# adapter-50-100mil-x6.net
KiCad netlist of a schematic drawn in Altium Designer
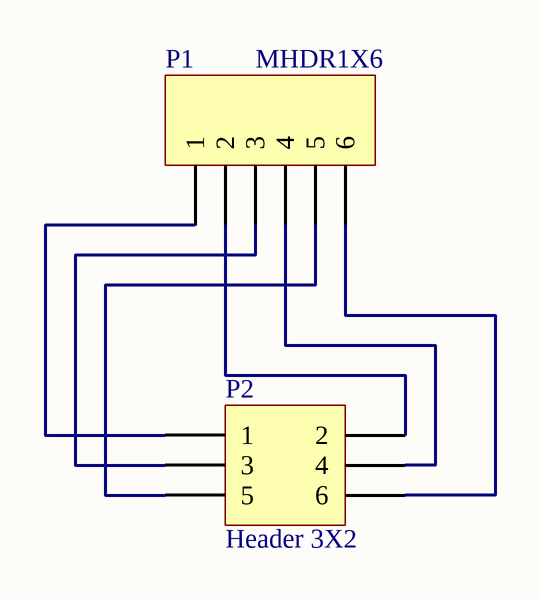
[diagram p0: adapter-50-100mil-x6.SchDoc]

(export (version "E")
  (design (tool "Eeschema 10.0.6"))
  (components
    (comp (ref "P1")
      (value "MHDR1X6")
      (footprint "MHDR1X6")
      (description "Header, 6-Pin")
      (fields (field (name "PUBLISHER") "Altium Limited"))
      (libsource (lib "Miscellaneous Connectors") (part "MHDR1X6"))
    )
    (comp (ref "P2")
      (value "Header 3X2")
      (footprint "HDR2X3")
      (description "Header, 3-Pin, Dual row")
      (fields (field (name "PUBLISHER") "Altium Limited"))
      (libsource (lib "Miscellaneous Connectors") (part "Header 3X2"))
    )
  )
  (nets
    (net (code "1") (name "Net-(P1-Pad1)") (class "Default")
      (node (ref "P1") (pin "1") (pinfunction "1_1") (pintype "passive"))
      (node (ref "P2") (pin "1") (pinfunction "1_1") (pintype "passive"))
    )
    (net (code "2") (name "Net-(P1-Pad2)") (class "Default")
      (node (ref "P1") (pin "2") (pinfunction "2_2") (pintype "passive"))
      (node (ref "P2") (pin "2") (pinfunction "2_2") (pintype "passive"))
    )
    (net (code "3") (name "Net-(P1-Pad3)") (class "Default")
      (node (ref "P1") (pin "3") (pinfunction "3_3") (pintype "passive"))
      (node (ref "P2") (pin "3") (pinfunction "3_3") (pintype "passive"))
    )
    (net (code "4") (name "Net-(P1-Pad4)") (class "Default")
      (node (ref "P1") (pin "4") (pinfunction "4_4") (pintype "passive"))
      (node (ref "P2") (pin "4") (pinfunction "4_4") (pintype "passive"))
    )
    (net (code "5") (name "Net-(P1-Pad5)") (class "Default")
      (node (ref "P1") (pin "5") (pinfunction "5_5") (pintype "passive"))
      (node (ref "P2") (pin "5") (pinfunction "5_5") (pintype "passive"))
    )
    (net (code "6") (name "Net-(P1-Pad6)") (class "Default")
      (node (ref "P1") (pin "6") (pinfunction "6_6") (pintype "passive"))
      (node (ref "P2") (pin "6") (pinfunction "6_6") (pintype "passive"))
    )
  )
)
